# lidar.net
KiCad netlist of a schematic drawn in EAGLE
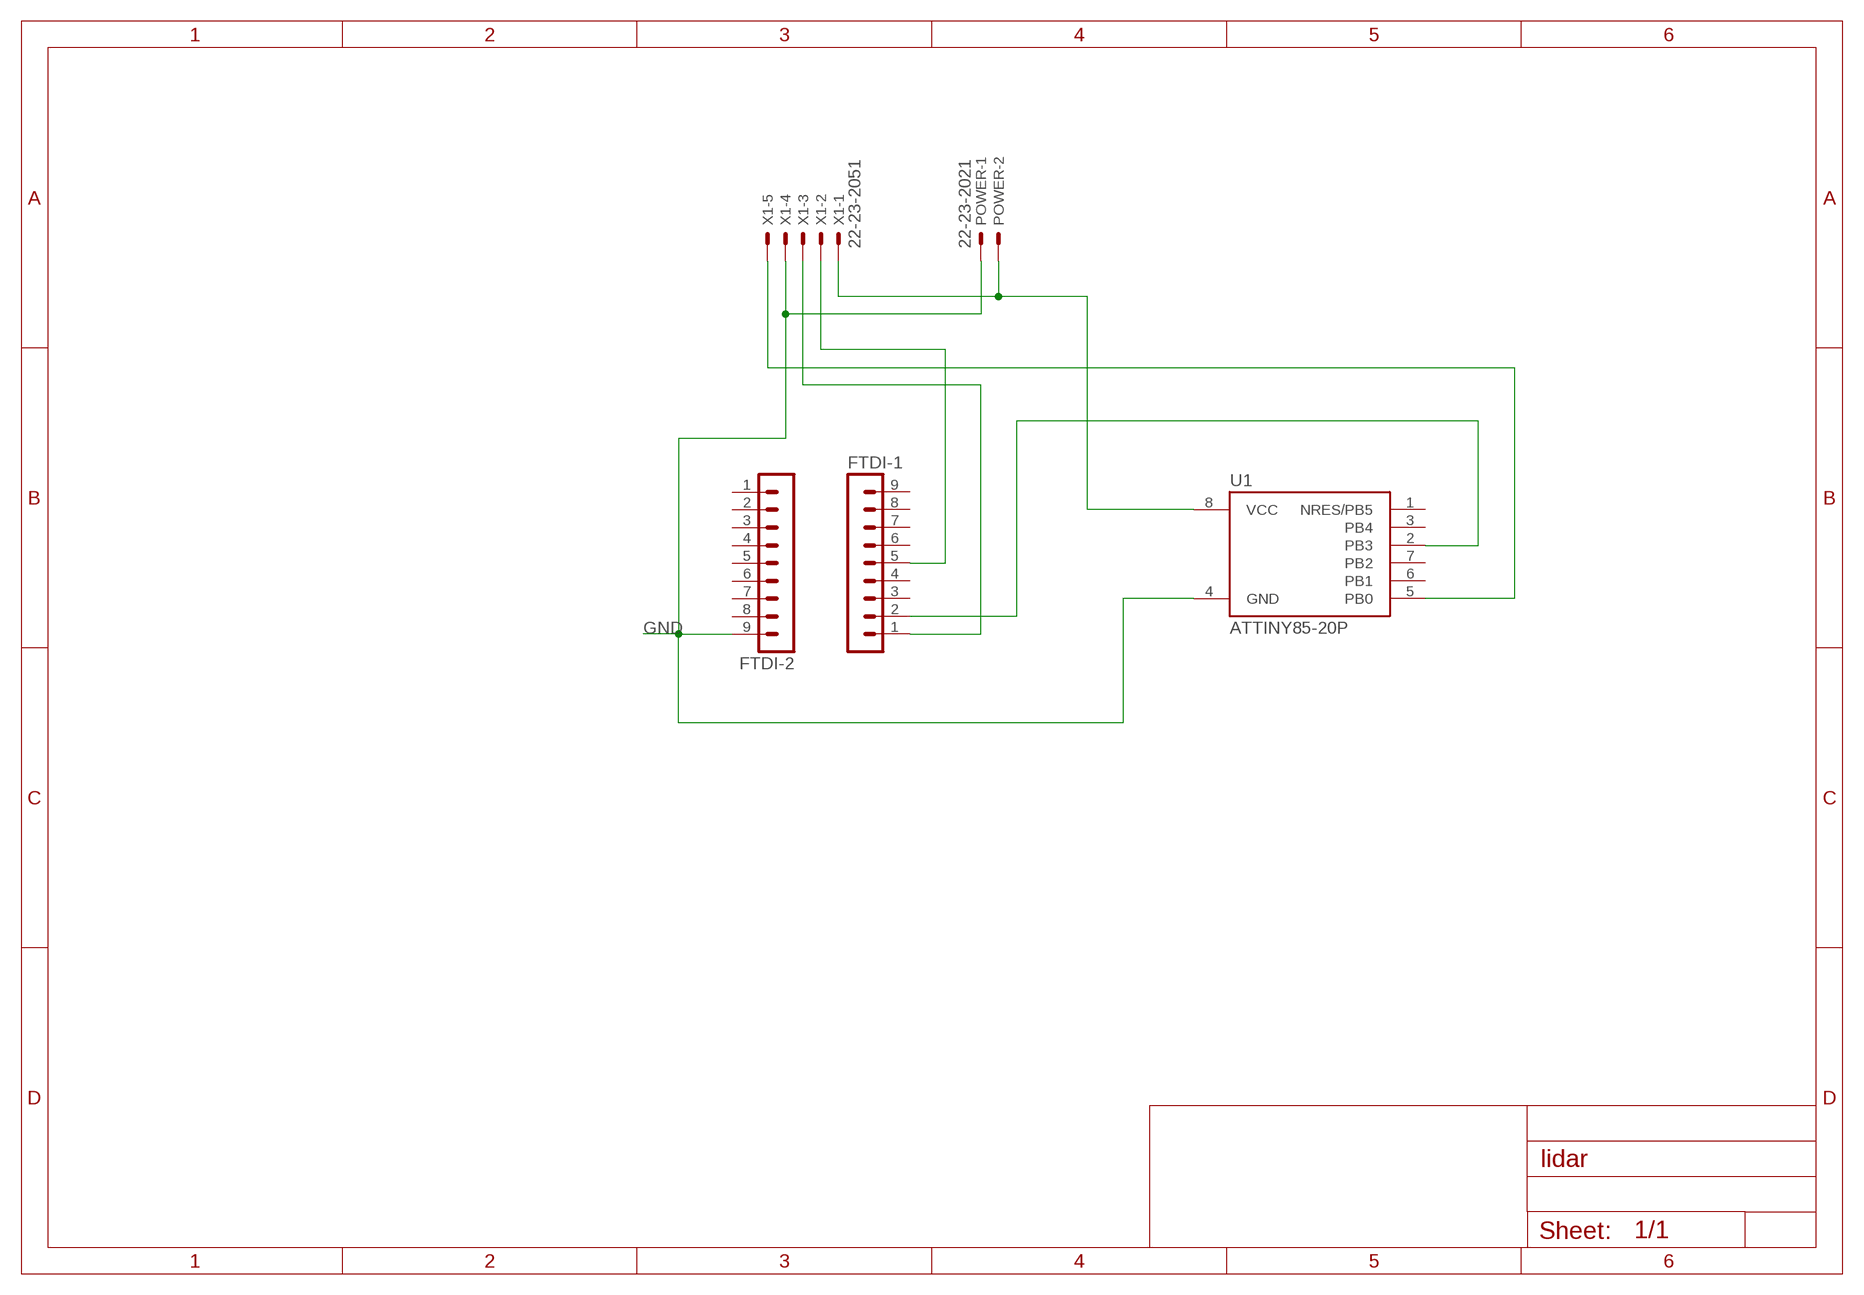
[diagram p0: schematic, sheet 1]

(export (version "E")
  (design (tool "Eeschema 10.0.6"))
  (components
    (comp (ref "FTDI-1")
      (value "MA09-1")
      (footprint "eagle-import:MA09-1")
      (libsource (lib "eagle-import") (part "MA09-1"))
    )
    (comp (ref "FTDI-2")
      (value "MA09-1")
      (footprint "eagle-import:MA09-1")
      (libsource (lib "eagle-import") (part "MA09-1"))
    )
    (comp (ref "POWER")
      (value "22-23-2021")
      (footprint "eagle-import:22-23-2021")
      (fields (field (name "MF") "MOLEX"))
      (libsource (lib "eagle-import") (part "22-23-2021"))
    )
    (comp (ref "U1")
      (value "ATTINY85-20P")
      (footprint "eagle-import:PDIP08_300MIL")
      (libsource (lib "eagle-import") (part "ATTINY85P-20"))
    )
    (comp (ref "X1")
      (value "22-23-2051")
      (footprint "eagle-import:22-23-2051")
      (fields (field (name "MF") "MOLEX"))
      (libsource (lib "eagle-import") (part "22-23-2051"))
    )
  )
  (nets
    (net (code "1") (name "/GND") (class "Default")
      (node (ref "FTDI-2") (pin "9") (pinfunction "9_9") (pintype "passive"))
      (node (ref "POWER") (pin "1") (pinfunction "S_1") (pintype "passive"))
      (node (ref "U1") (pin "4") (pinfunction "GND_4") (pintype "power_in"))
      (node (ref "X1") (pin "4") (pinfunction "S_4") (pintype "passive"))
    )
    (net (code "2") (name "Net-(POWERB-S)") (class "Default")
      (node (ref "POWER") (pin "2") (pinfunction "S_2") (pintype "passive"))
      (node (ref "U1") (pin "8") (pinfunction "VCC_8") (pintype "power_in"))
      (node (ref "X1") (pin "1") (pinfunction "S_1") (pintype "passive"))
    )
    (net (code "3") (name "Net-(U1-PB0)") (class "Default")
      (node (ref "U1") (pin "5") (pinfunction "PB0_5") (pintype "bidirectional"))
      (node (ref "X1") (pin "5") (pinfunction "S_5") (pintype "passive"))
    )
    (net (code "4") (name "Net-(U1-PB3)") (class "Default")
      (node (ref "FTDI-1") (pin "2") (pinfunction "2_2") (pintype "passive"))
      (node (ref "U1") (pin "2") (pinfunction "PB3_2") (pintype "bidirectional"))
    )
    (net (code "5") (name "Net-(X1B-S)") (class "Default")
      (node (ref "FTDI-1") (pin "5") (pinfunction "5_5") (pintype "passive"))
      (node (ref "X1") (pin "2") (pinfunction "S_2") (pintype "passive"))
    )
    (net (code "6") (name "Net-(X1C-S)") (class "Default")
      (node (ref "FTDI-1") (pin "1") (pinfunction "1_1") (pintype "passive"))
      (node (ref "X1") (pin "3") (pinfunction "S_3") (pintype "passive"))
    )
    (net (code "7") (name "unconnected-(FTDI-1-Pad3)") (class "Default")
      (node (ref "FTDI-1") (pin "3") (pinfunction "3_3") (pintype "passive"))
    )
    (net (code "8") (name "unconnected-(FTDI-1-Pad4)") (class "Default")
      (node (ref "FTDI-1") (pin "4") (pinfunction "4_4") (pintype "passive"))
    )
    (net (code "9") (name "unconnected-(FTDI-1-Pad6)") (class "Default")
      (node (ref "FTDI-1") (pin "6") (pinfunction "6_6") (pintype "passive"))
    )
    (net (code "10") (name "unconnected-(FTDI-1-Pad7)") (class "Default")
      (node (ref "FTDI-1") (pin "7") (pinfunction "7_7") (pintype "passive"))
    )
    (net (code "11") (name "unconnected-(FTDI-1-Pad8)") (class "Default")
      (node (ref "FTDI-1") (pin "8") (pinfunction "8_8") (pintype "passive"))
    )
    (net (code "12") (name "unconnected-(FTDI-1-Pad9)") (class "Default")
      (node (ref "FTDI-1") (pin "9") (pinfunction "9_9") (pintype "passive"))
    )
    (net (code "13") (name "unconnected-(FTDI-2-Pad1)") (class "Default")
      (node (ref "FTDI-2") (pin "1") (pinfunction "1_1") (pintype "passive"))
    )
    (net (code "14") (name "unconnected-(FTDI-2-Pad2)") (class "Default")
      (node (ref "FTDI-2") (pin "2") (pinfunction "2_2") (pintype "passive"))
    )
    (net (code "15") (name "unconnected-(FTDI-2-Pad3)") (class "Default")
      (node (ref "FTDI-2") (pin "3") (pinfunction "3_3") (pintype "passive"))
    )
    (net (code "16") (name "unconnected-(FTDI-2-Pad4)") (class "Default")
      (node (ref "FTDI-2") (pin "4") (pinfunction "4_4") (pintype "passive"))
    )
    (net (code "17") (name "unconnected-(FTDI-2-Pad5)") (class "Default")
      (node (ref "FTDI-2") (pin "5") (pinfunction "5_5") (pintype "passive"))
    )
    (net (code "18") (name "unconnected-(FTDI-2-Pad6)") (class "Default")
      (node (ref "FTDI-2") (pin "6") (pinfunction "6_6") (pintype "passive"))
    )
    (net (code "19") (name "unconnected-(FTDI-2-Pad7)") (class "Default")
      (node (ref "FTDI-2") (pin "7") (pinfunction "7_7") (pintype "passive"))
    )
    (net (code "20") (name "unconnected-(FTDI-2-Pad8)") (class "Default")
      (node (ref "FTDI-2") (pin "8") (pinfunction "8_8") (pintype "passive"))
    )
    (net (code "21") (name "unconnected-(U1-NRES{slash}PB5-Pad1)") (class "Default")
      (node (ref "U1") (pin "1") (pinfunction "NRES/PB5_1") (pintype "bidirectional"))
    )
    (net (code "22") (name "unconnected-(U1-PB1-Pad6)") (class "Default")
      (node (ref "U1") (pin "6") (pinfunction "PB1_6") (pintype "bidirectional"))
    )
    (net (code "23") (name "unconnected-(U1-PB2-Pad7)") (class "Default")
      (node (ref "U1") (pin "7") (pinfunction "PB2_7") (pintype "bidirectional"))
    )
    (net (code "24") (name "unconnected-(U1-PB4-Pad3)") (class "Default")
      (node (ref "U1") (pin "3") (pinfunction "PB4_3") (pintype "bidirectional"))
    )
  )
)
